# Revision_A.net
KiCad netlist of a schematic drawn in EAGLE
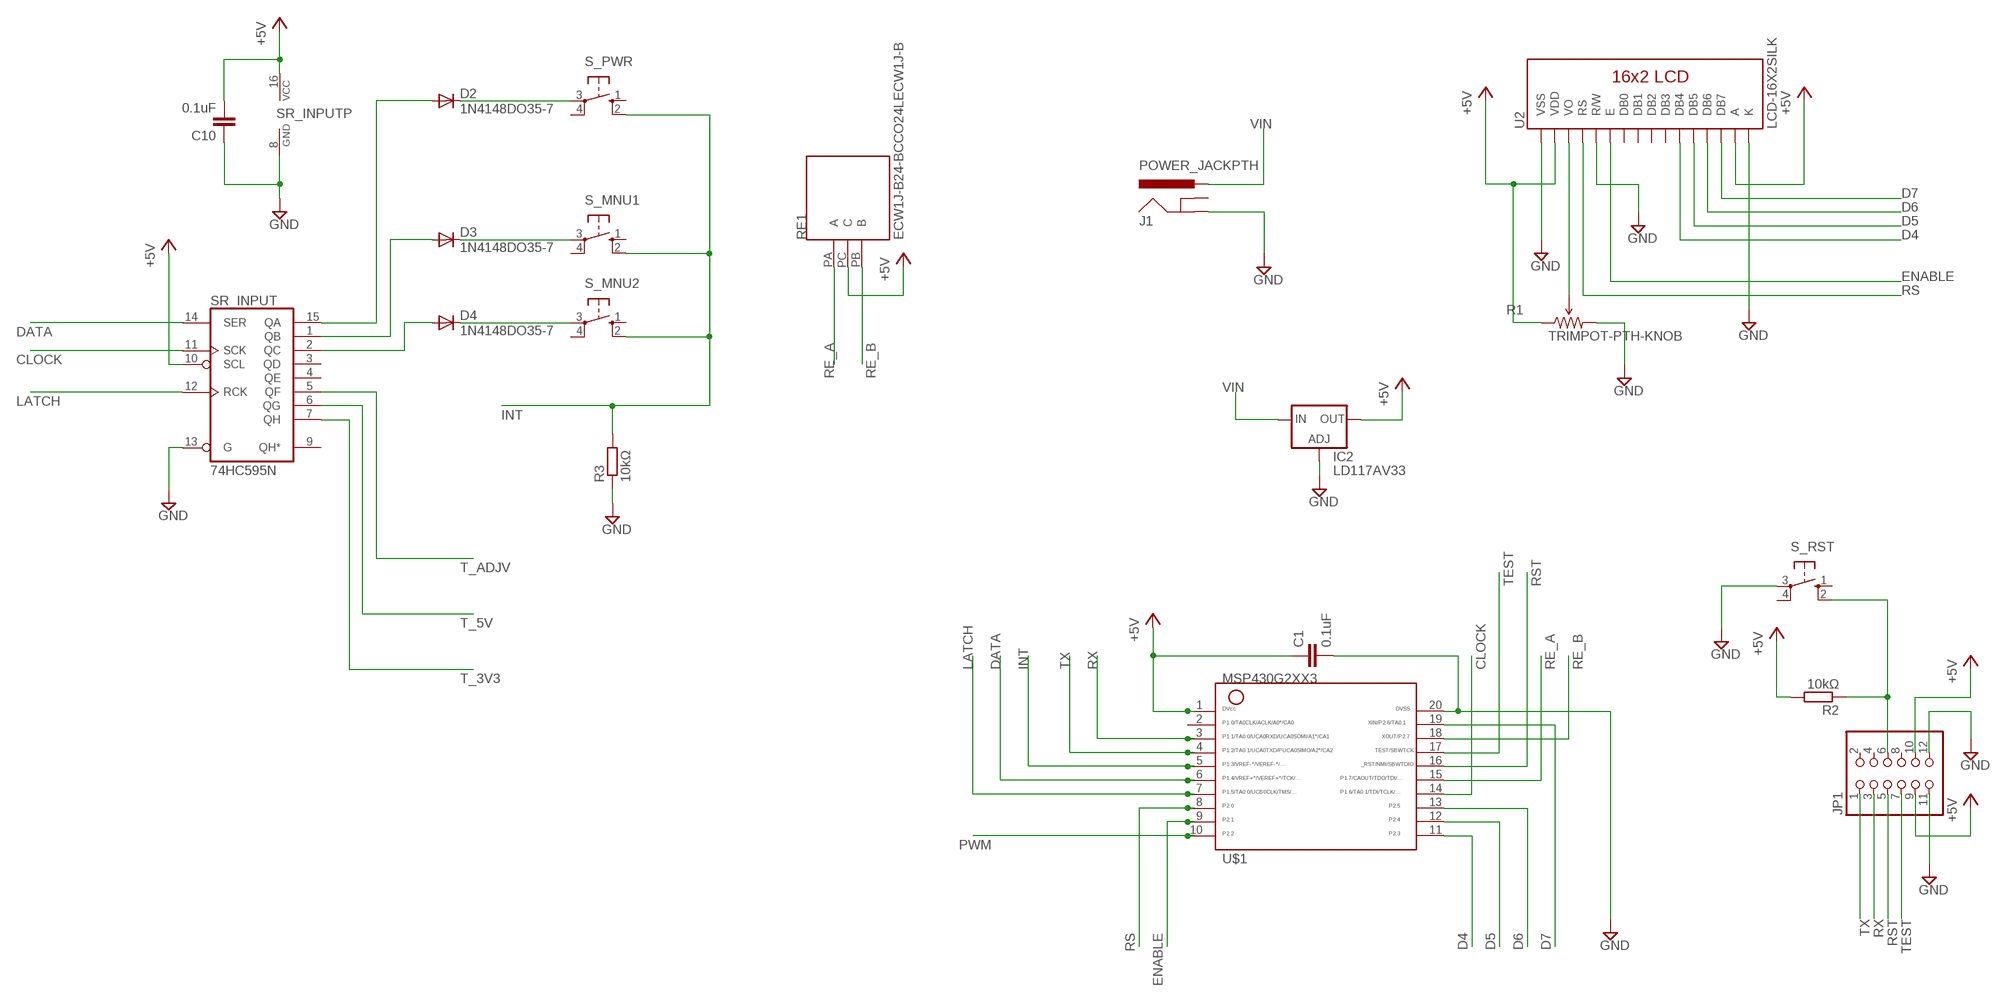
[diagram p0: schematic, sheet 1, part 1 of 2]
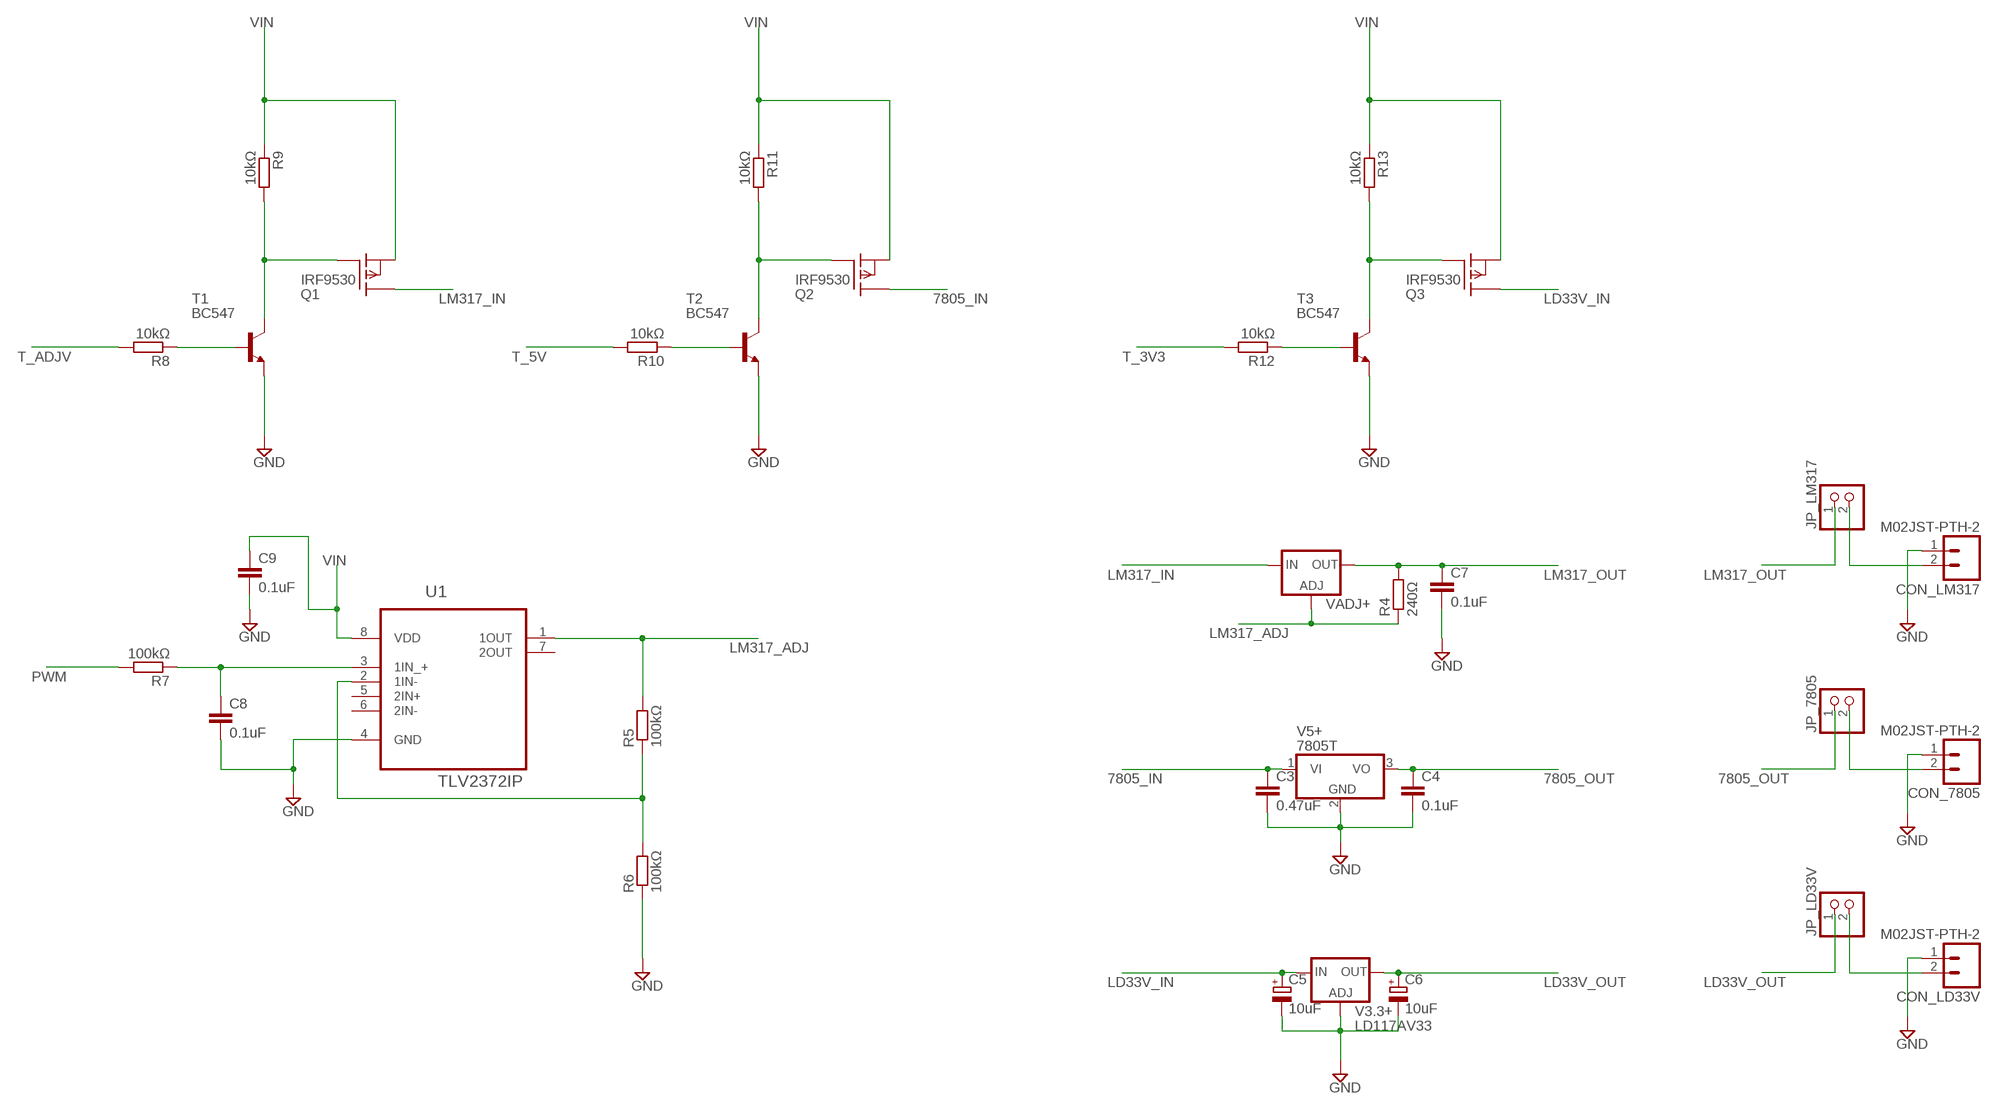
[diagram p1: schematic, sheet 1, part 2 of 2]

(export (version "E")
  (design (tool "Eeschema 10.0.6"))
  (components
    (comp (ref "C1")
      (value "0.1uF")
      (footprint "eagle-import:C025-025X050")
      (libsource (lib "eagle-import") (part "C-EU025-025X050"))
    )
    (comp (ref "C3")
      (value "0.47uF")
      (footprint "eagle-import:C025-025X050")
      (libsource (lib "eagle-import") (part "C-EU025-025X050"))
    )
    (comp (ref "C4")
      (value "0.1uF")
      (footprint "eagle-import:C025-025X050")
      (libsource (lib "eagle-import") (part "C-EU025-025X050"))
    )
    (comp (ref "C5")
      (value "10uF")
      (footprint "eagle-import:E2,5-6")
      (libsource (lib "eagle-import") (part "CPOL-EUE2.5-6"))
    )
    (comp (ref "C6")
      (value "10uF")
      (footprint "eagle-import:E2,5-6")
      (libsource (lib "eagle-import") (part "CPOL-EUE2.5-6"))
    )
    (comp (ref "C7")
      (value "0.1uF")
      (footprint "eagle-import:C025-025X050")
      (libsource (lib "eagle-import") (part "C-EU025-025X050"))
    )
    (comp (ref "C8")
      (value "0.1uF")
      (footprint "eagle-import:C025-025X050")
      (libsource (lib "eagle-import") (part "C-EU025-025X050"))
    )
    (comp (ref "C9")
      (value "0.1uF")
      (footprint "eagle-import:C025-025X050")
      (libsource (lib "eagle-import") (part "C-EU025-025X050"))
    )
    (comp (ref "C10")
      (value "0.1uF")
      (footprint "eagle-import:C025-025X050")
      (libsource (lib "eagle-import") (part "C-EU025-025X050"))
    )
    (comp (ref "CON_7805")
      (value "M02JST-PTH-2")
      (footprint "eagle-import:JST-2-PTH")
      (libsource (lib "eagle-import") (part "M02JST-PTH-2"))
    )
    (comp (ref "CON_LD33V")
      (value "M02JST-PTH-2")
      (footprint "eagle-import:JST-2-PTH")
      (libsource (lib "eagle-import") (part "M02JST-PTH-2"))
    )
    (comp (ref "CON_LM317")
      (value "M02JST-PTH-2")
      (footprint "eagle-import:JST-2-PTH")
      (libsource (lib "eagle-import") (part "M02JST-PTH-2"))
    )
    (comp (ref "D2")
      (value "1N4148DO35-7")
      (footprint "eagle-import:DO35-7")
      (libsource (lib "eagle-import") (part "1N4148DO35-7"))
    )
    (comp (ref "D3")
      (value "1N4148DO35-7")
      (footprint "eagle-import:DO35-7")
      (libsource (lib "eagle-import") (part "1N4148DO35-7"))
    )
    (comp (ref "D4")
      (value "1N4148DO35-7")
      (footprint "eagle-import:DO35-7")
      (libsource (lib "eagle-import") (part "1N4148DO35-7"))
    )
    (comp (ref "IC2")
      (value "LD117AV33")
      (footprint "eagle-import:TO220L1")
      (libsource (lib "eagle-import") (part "LD117A?V33"))
    )
    (comp (ref "J1")
      (value "POWER_JACKPTH")
      (footprint "eagle-import:POWER_JACK_PTH")
      (libsource (lib "eagle-import") (part "POWER_JACKPTH"))
    )
    (comp (ref "JP1")
      (value "PINHD-2X6")
      (footprint "eagle-import:2X06")
      (libsource (lib "eagle-import") (part "PINHD-2X6"))
    )
    (comp (ref "JP_7805")
      (value "PINHD-1X2")
      (footprint "eagle-import:1X02")
      (libsource (lib "eagle-import") (part "PINHD-1X2"))
    )
    (comp (ref "JP_LD33V")
      (value "PINHD-1X2")
      (footprint "eagle-import:1X02")
      (libsource (lib "eagle-import") (part "PINHD-1X2"))
    )
    (comp (ref "JP_LM317")
      (value "PINHD-1X2")
      (footprint "eagle-import:1X02")
      (libsource (lib "eagle-import") (part "PINHD-1X2"))
    )
    (comp (ref "Q1")
      (value "IRF9530")
      (footprint "eagle-import:TO220")
      (libsource (lib "eagle-import") (part "IRF9530"))
    )
    (comp (ref "Q2")
      (value "IRF9530")
      (footprint "eagle-import:TO220")
      (libsource (lib "eagle-import") (part "IRF9530"))
    )
    (comp (ref "Q3")
      (value "IRF9530")
      (footprint "eagle-import:TO220")
      (libsource (lib "eagle-import") (part "IRF9530"))
    )
    (comp (ref "R1")
      (value "TRIMPOT-PTH-KNOB")
      (footprint "eagle-import:3386U")
      (libsource (lib "eagle-import") (part "TRIMPOT-PTH-KNOB"))
    )
    (comp (ref "R2")
      (value "10kΩ")
      (footprint "eagle-import:0207_10")
      (libsource (lib "eagle-import") (part "R-EU_0207/10"))
    )
    (comp (ref "R3")
      (value "10kΩ")
      (footprint "eagle-import:0207_10")
      (libsource (lib "eagle-import") (part "R-EU_0207/10"))
    )
    (comp (ref "R4")
      (value "240Ω")
      (footprint "eagle-import:0207_10")
      (libsource (lib "eagle-import") (part "R-EU_0207/10"))
    )
    (comp (ref "R5")
      (value "100kΩ")
      (footprint "eagle-import:0207_10")
      (libsource (lib "eagle-import") (part "R-EU_0207/10"))
    )
    (comp (ref "R6")
      (value "100kΩ")
      (footprint "eagle-import:0207_10")
      (libsource (lib "eagle-import") (part "R-EU_0207/10"))
    )
    (comp (ref "R7")
      (value "100kΩ")
      (footprint "eagle-import:0207_10")
      (libsource (lib "eagle-import") (part "R-EU_0207/10"))
    )
    (comp (ref "R8")
      (value "10kΩ")
      (footprint "eagle-import:0207_10")
      (libsource (lib "eagle-import") (part "R-EU_0207/10"))
    )
    (comp (ref "R9")
      (value "10kΩ")
      (footprint "eagle-import:0207_10")
      (libsource (lib "eagle-import") (part "R-EU_0207/10"))
    )
    (comp (ref "R10")
      (value "10kΩ")
      (footprint "eagle-import:0207_10")
      (libsource (lib "eagle-import") (part "R-EU_0207/10"))
    )
    (comp (ref "R11")
      (value "10kΩ")
      (footprint "eagle-import:0207_10")
      (libsource (lib "eagle-import") (part "R-EU_0207/10"))
    )
    (comp (ref "R12")
      (value "10kΩ")
      (footprint "eagle-import:0207_10")
      (libsource (lib "eagle-import") (part "R-EU_0207/10"))
    )
    (comp (ref "R13")
      (value "10kΩ")
      (footprint "eagle-import:0207_10")
      (libsource (lib "eagle-import") (part "R-EU_0207/10"))
    )
    (comp (ref "RE1")
      (value "ECW1J-B24-BCCO24LECW1J-B")
      (footprint "eagle-import:ECW1J-B")
      (libsource (lib "eagle-import") (part "ECW1J-B24-BCCO24LECW1J-B"))
    )
    (comp (ref "SR_INPUT")
      (value "74HC595N")
      (footprint "eagle-import:DIL16")
      (libsource (lib "eagle-import") (part "74595NHC"))
    )
    (comp (ref "S_MNU1")
      (value "10-XX")
      (footprint "eagle-import:B3F-10XX")
      (fields (field (name "MPN") "B3F-1000"))
      (libsource (lib "eagle-import") (part "10-XX"))
    )
    (comp (ref "S_MNU2")
      (value "10-XX")
      (footprint "eagle-import:B3F-10XX")
      (fields (field (name "MPN") "B3F-1000"))
      (libsource (lib "eagle-import") (part "10-XX"))
    )
    (comp (ref "S_PWR")
      (value "10-XX")
      (footprint "eagle-import:B3F-10XX")
      (fields (field (name "MPN") "B3F-1000"))
      (libsource (lib "eagle-import") (part "10-XX"))
    )
    (comp (ref "S_RST")
      (value "10-XX")
      (footprint "eagle-import:B3F-10XX")
      (fields (field (name "MPN") "B3F-1000"))
      (libsource (lib "eagle-import") (part "10-XX"))
    )
    (comp (ref "T1")
      (value "BC547")
      (footprint "eagle-import:TO92")
      (libsource (lib "eagle-import") (part "BC547"))
    )
    (comp (ref "T2")
      (value "BC547")
      (footprint "eagle-import:TO92")
      (libsource (lib "eagle-import") (part "BC547"))
    )
    (comp (ref "T3")
      (value "BC547")
      (footprint "eagle-import:TO92")
      (libsource (lib "eagle-import") (part "BC547"))
    )
    (comp (ref "U$1")
      (value "G2XX3---N20")
      (footprint "eagle-import:N20")
      (libsource (lib "eagle-import") (part "G2XX3---N20"))
    )
    (comp (ref "U1")
      (value "TLV2372IP")
      (footprint "eagle-import:DIP254P762X508-8")
      (libsource (lib "eagle-import") (part "TLV2372IP"))
    )
    (comp (ref "U2")
      (value "LCD-16X2SILK")
      (footprint "eagle-import:LCD-16X2")
      (libsource (lib "eagle-import") (part "LCD-16X2SILK"))
    )
    (comp (ref "V3.3+")
      (value "LD117AV33")
      (footprint "eagle-import:TO220L1")
      (libsource (lib "eagle-import") (part "LD117A?V33"))
    )
    (comp (ref "V5+")
      (value "7805T")
      (footprint "eagle-import:TO220H")
      (libsource (lib "eagle-import") (part "78T05"))
    )
    (comp (ref "VADJ+")
      (value "LM317TL")
      (footprint "eagle-import:317TL")
      (libsource (lib "eagle-import") (part "LM317TL"))
    )
  )
  (nets
    (net (code "1") (name "+5V") (class "Default")
      (node (ref "C1") (pin "1") (pinfunction "1_1") (pintype "passive"))
      (node (ref "C10") (pin "2") (pinfunction "2_2") (pintype "passive"))
      (node (ref "IC2") (pin "2") (pinfunction "OUT_2") (pintype "passive"))
      (node (ref "JP1") (pin "10") (pinfunction "10_10") (pintype "passive"))
      (node (ref "JP1") (pin "9") (pinfunction "9_9") (pintype "passive"))
      (node (ref "R1") (pin "1") (pinfunction "CCW_1") (pintype "passive"))
      (node (ref "R2") (pin "2") (pinfunction "2_2") (pintype "passive"))
      (node (ref "RE1") (pin "PC") (pinfunction "C_PC") (pintype "bidirectional"))
      (node (ref "SR_INPUT") (pin "10") (pinfunction "SCL_10") (pintype "input"))
      (node (ref "SR_INPUT") (pin "16") (pinfunction "VCC_16") (pintype "power_in"))
      (node (ref "U$1") (pin "1") (pinfunction "1_1") (pintype "bidirectional"))
      (node (ref "U2") (pin "15") (pinfunction "A_15") (pintype "power_in"))
      (node (ref "U2") (pin "2") (pinfunction "VDD_2") (pintype "power_in"))
    )
    (net (code "2") (name "/7805_IN") (class "Default")
      (node (ref "C3") (pin "1") (pinfunction "1_1") (pintype "passive"))
      (node (ref "Q2") (pin "2") (pinfunction "D_2") (pintype "passive"))
      (node (ref "V5+") (pin "1") (pinfunction "VI_1") (pintype "input"))
    )
    (net (code "3") (name "/7805_OUT") (class "Default")
      (node (ref "C4") (pin "1") (pinfunction "1_1") (pintype "passive"))
      (node (ref "JP_7805") (pin "1") (pinfunction "1_1") (pintype "passive"))
      (node (ref "V5+") (pin "3") (pinfunction "VO_3") (pintype "passive"))
    )
    (net (code "4") (name "/CLOCK") (class "Default")
      (node (ref "SR_INPUT") (pin "11") (pinfunction "SCK_11") (pintype "input"))
      (node (ref "U$1") (pin "14") (pinfunction "14_14") (pintype "bidirectional"))
    )
    (net (code "5") (name "/D4") (class "Default")
      (node (ref "U$1") (pin "11") (pinfunction "11_11") (pintype "bidirectional"))
      (node (ref "U2") (pin "11") (pinfunction "DB4_11") (pintype "bidirectional"))
    )
    (net (code "6") (name "/D5") (class "Default")
      (node (ref "U$1") (pin "12") (pinfunction "12_12") (pintype "bidirectional"))
      (node (ref "U2") (pin "12") (pinfunction "DB5_12") (pintype "bidirectional"))
    )
    (net (code "7") (name "/D6") (class "Default")
      (node (ref "U$1") (pin "13") (pinfunction "13_13") (pintype "bidirectional"))
      (node (ref "U2") (pin "13") (pinfunction "DB6_13") (pintype "bidirectional"))
    )
    (net (code "8") (name "/D7") (class "Default")
      (node (ref "U$1") (pin "19") (pinfunction "19_19") (pintype "bidirectional"))
      (node (ref "U2") (pin "14") (pinfunction "DB7_14") (pintype "bidirectional"))
    )
    (net (code "9") (name "/DATA") (class "Default")
      (node (ref "SR_INPUT") (pin "14") (pinfunction "SER_14") (pintype "input"))
      (node (ref "U$1") (pin "6") (pinfunction "6_6") (pintype "bidirectional"))
    )
    (net (code "10") (name "/ENABLE") (class "Default")
      (node (ref "U$1") (pin "9") (pinfunction "9_9") (pintype "bidirectional"))
      (node (ref "U2") (pin "6") (pinfunction "E_6") (pintype "input"))
    )
    (net (code "11") (name "/INT") (class "Default")
      (node (ref "R3") (pin "2") (pinfunction "2_2") (pintype "passive"))
      (node (ref "S_MNU1") (pin "2") (pinfunction "S1_2") (pintype "passive"))
      (node (ref "S_MNU2") (pin "2") (pinfunction "S1_2") (pintype "passive"))
      (node (ref "S_PWR") (pin "2") (pinfunction "S1_2") (pintype "passive"))
      (node (ref "U$1") (pin "5") (pinfunction "5_5") (pintype "bidirectional"))
    )
    (net (code "12") (name "/LATCH") (class "Default")
      (node (ref "SR_INPUT") (pin "12") (pinfunction "RCK_12") (pintype "input"))
      (node (ref "U$1") (pin "7") (pinfunction "7_7") (pintype "bidirectional"))
    )
    (net (code "13") (name "/LD33V_IN") (class "Default")
      (node (ref "C5") (pin "+") (pinfunction "+_+") (pintype "passive"))
      (node (ref "Q3") (pin "2") (pinfunction "D_2") (pintype "passive"))
      (node (ref "V3.3+") (pin "3") (pinfunction "IN_3") (pintype "input"))
    )
    (net (code "14") (name "/LD33V_OUT") (class "Default")
      (node (ref "C6") (pin "+") (pinfunction "+_+") (pintype "passive"))
      (node (ref "JP_LD33V") (pin "1") (pinfunction "1_1") (pintype "passive"))
      (node (ref "V3.3+") (pin "2") (pinfunction "OUT_2") (pintype "passive"))
    )
    (net (code "15") (name "/LM317_ADJ") (class "Default")
      (node (ref "R4") (pin "1") (pinfunction "1_1") (pintype "passive"))
      (node (ref "R5") (pin "2") (pinfunction "2_2") (pintype "passive"))
      (node (ref "U1") (pin "1") (pinfunction "1OUT_1") (pintype "output"))
      (node (ref "VADJ+") (pin "1") (pinfunction "ADJ_1") (pintype "input"))
    )
    (net (code "16") (name "/LM317_IN") (class "Default")
      (node (ref "Q1") (pin "2") (pinfunction "D_2") (pintype "passive"))
      (node (ref "VADJ+") (pin "3") (pinfunction "IN_3") (pintype "input"))
    )
    (net (code "17") (name "/LM317_OUT") (class "Default")
      (node (ref "C7") (pin "1") (pinfunction "1_1") (pintype "passive"))
      (node (ref "JP_LM317") (pin "1") (pinfunction "1_1") (pintype "passive"))
      (node (ref "R4") (pin "2") (pinfunction "2_2") (pintype "passive"))
      (node (ref "VADJ+") (pin "2") (pinfunction "OUT_2") (pintype "passive"))
    )
    (net (code "18") (name "/PWM") (class "Default")
      (node (ref "R7") (pin "2") (pinfunction "2_2") (pintype "passive"))
      (node (ref "U$1") (pin "10") (pinfunction "10_10") (pintype "bidirectional"))
    )
    (net (code "19") (name "/RE_A") (class "Default")
      (node (ref "RE1") (pin "PA") (pinfunction "A_PA") (pintype "bidirectional"))
      (node (ref "U$1") (pin "15") (pinfunction "15_15") (pintype "bidirectional"))
    )
    (net (code "20") (name "/RE_B") (class "Default")
      (node (ref "RE1") (pin "PB") (pinfunction "B_PB") (pintype "bidirectional"))
      (node (ref "U$1") (pin "18") (pinfunction "18_18") (pintype "bidirectional"))
    )
    (net (code "21") (name "/RS") (class "Default")
      (node (ref "U$1") (pin "8") (pinfunction "8_8") (pintype "bidirectional"))
      (node (ref "U2") (pin "4") (pinfunction "RS_4") (pintype "input"))
    )
    (net (code "22") (name "/RST") (class "Default")
      (node (ref "JP1") (pin "5") (pinfunction "5_5") (pintype "passive"))
      (node (ref "U$1") (pin "16") (pinfunction "16_16") (pintype "bidirectional"))
    )
    (net (code "23") (name "/RX") (class "Default")
      (node (ref "JP1") (pin "3") (pinfunction "3_3") (pintype "passive"))
      (node (ref "U$1") (pin "3") (pinfunction "3_3") (pintype "bidirectional"))
    )
    (net (code "24") (name "/TEST") (class "Default")
      (node (ref "JP1") (pin "7") (pinfunction "7_7") (pintype "passive"))
      (node (ref "U$1") (pin "17") (pinfunction "17_17") (pintype "bidirectional"))
    )
    (net (code "25") (name "/TX") (class "Default")
      (node (ref "JP1") (pin "1") (pinfunction "1_1") (pintype "passive"))
      (node (ref "U$1") (pin "4") (pinfunction "4_4") (pintype "bidirectional"))
    )
    (net (code "26") (name "/T_3V3") (class "Default")
      (node (ref "R12") (pin "2") (pinfunction "2_2") (pintype "passive"))
      (node (ref "SR_INPUT") (pin "7") (pinfunction "QH_7") (pintype "tri_state"))
    )
    (net (code "27") (name "/T_5V") (class "Default")
      (node (ref "R10") (pin "2") (pinfunction "2_2") (pintype "passive"))
      (node (ref "SR_INPUT") (pin "6") (pinfunction "QG_6") (pintype "tri_state"))
    )
    (net (code "28") (name "/T_ADJV") (class "Default")
      (node (ref "R8") (pin "2") (pinfunction "2_2") (pintype "passive"))
      (node (ref "SR_INPUT") (pin "5") (pinfunction "QF_5") (pintype "tri_state"))
    )
    (net (code "29") (name "/VIN") (class "Default")
      (node (ref "C9") (pin "1") (pinfunction "1_1") (pintype "passive"))
      (node (ref "IC2") (pin "3") (pinfunction "IN_3") (pintype "input"))
      (node (ref "J1") (pin "PWR") (pinfunction "PWR_PWR") (pintype "bidirectional"))
      (node (ref "Q1") (pin "3") (pinfunction "S_3") (pintype "passive"))
      (node (ref "Q2") (pin "3") (pinfunction "S_3") (pintype "passive"))
      (node (ref "Q3") (pin "3") (pinfunction "S_3") (pintype "passive"))
      (node (ref "R11") (pin "1") (pinfunction "1_1") (pintype "passive"))
      (node (ref "R13") (pin "1") (pinfunction "1_1") (pintype "passive"))
      (node (ref "R9") (pin "1") (pinfunction "1_1") (pintype "passive"))
      (node (ref "U1") (pin "8") (pinfunction "VDD_8") (pintype "power_in"))
    )
    (net (code "30") (name "GND") (class "Default")
      (node (ref "C1") (pin "2") (pinfunction "2_2") (pintype "passive"))
      (node (ref "C10") (pin "1") (pinfunction "1_1") (pintype "passive"))
      (node (ref "C3") (pin "2") (pinfunction "2_2") (pintype "passive"))
      (node (ref "C4") (pin "2") (pinfunction "2_2") (pintype "passive"))
      (node (ref "C5") (pin "-") (pinfunction "-_-") (pintype "passive"))
      (node (ref "C6") (pin "-") (pinfunction "-_-") (pintype "passive"))
      (node (ref "C7") (pin "2") (pinfunction "2_2") (pintype "passive"))
      (node (ref "C8") (pin "2") (pinfunction "2_2") (pintype "passive"))
      (node (ref "C9") (pin "2") (pinfunction "2_2") (pintype "passive"))
      (node (ref "CON_7805") (pin "1") (pinfunction "1_1") (pintype "passive"))
      (node (ref "CON_LD33V") (pin "1") (pinfunction "1_1") (pintype "passive"))
      (node (ref "CON_LM317") (pin "1") (pinfunction "1_1") (pintype "passive"))
      (node (ref "IC2") (pin "1") (pinfunction "ADJ_1") (pintype "input"))
      (node (ref "J1") (pin "GND") (pinfunction "GND_GND") (pintype "bidirectional"))
      (node (ref "JP1") (pin "11") (pinfunction "11_11") (pintype "passive"))
      (node (ref "JP1") (pin "12") (pinfunction "12_12") (pintype "passive"))
      (node (ref "R1") (pin "3") (pinfunction "CW_3") (pintype "passive"))
      (node (ref "R3") (pin "1") (pinfunction "1_1") (pintype "passive"))
      (node (ref "R6") (pin "1") (pinfunction "1_1") (pintype "passive"))
      (node (ref "SR_INPUT") (pin "13") (pinfunction "G_13") (pintype "input"))
      (node (ref "SR_INPUT") (pin "8") (pinfunction "GND_8") (pintype "power_in"))
      (node (ref "S_RST") (pin "3") (pinfunction "P_3") (pintype "passive"))
      (node (ref "T1") (pin "1") (pinfunction "E_1") (pintype "passive"))
      (node (ref "T2") (pin "1") (pinfunction "E_1") (pintype "passive"))
      (node (ref "T3") (pin "1") (pinfunction "E_1") (pintype "passive"))
      (node (ref "U$1") (pin "20") (pinfunction "20_20") (pintype "bidirectional"))
      (node (ref "U1") (pin "4") (pinfunction "GND_4") (pintype "passive"))
      (node (ref "U2") (pin "1") (pinfunction "VSS_1") (pintype "power_in"))
      (node (ref "U2") (pin "16") (pinfunction "K_16") (pintype "power_in"))
      (node (ref "U2") (pin "5") (pinfunction "R/W_5") (pintype "input"))
      (node (ref "V3.3+") (pin "1") (pinfunction "ADJ_1") (pintype "input"))
      (node (ref "V5+") (pin "2") (pinfunction "GND_2") (pintype "passive"))
    )
    (net (code "31") (name "Net-(CON_7805-Pad2)") (class "Default")
      (node (ref "CON_7805") (pin "2") (pinfunction "2_2") (pintype "passive"))
      (node (ref "JP_7805") (pin "2") (pinfunction "2_2") (pintype "passive"))
    )
    (net (code "32") (name "Net-(CON_LD33V-Pad2)") (class "Default")
      (node (ref "CON_LD33V") (pin "2") (pinfunction "2_2") (pintype "passive"))
      (node (ref "JP_LD33V") (pin "2") (pinfunction "2_2") (pintype "passive"))
    )
    (net (code "33") (name "Net-(CON_LM317-Pad2)") (class "Default")
      (node (ref "CON_LM317") (pin "2") (pinfunction "2_2") (pintype "passive"))
      (node (ref "JP_LM317") (pin "2") (pinfunction "2_2") (pintype "passive"))
    )
    (net (code "34") (name "Net-(Q1-G)") (class "Default")
      (node (ref "Q1") (pin "1") (pinfunction "G_1") (pintype "passive"))
      (node (ref "R9") (pin "2") (pinfunction "2_2") (pintype "passive"))
      (node (ref "T1") (pin "3") (pinfunction "C_3") (pintype "passive"))
    )
    (net (code "35") (name "Net-(Q2-G)") (class "Default")
      (node (ref "Q2") (pin "1") (pinfunction "G_1") (pintype "passive"))
      (node (ref "R11") (pin "2") (pinfunction "2_2") (pintype "passive"))
      (node (ref "T2") (pin "3") (pinfunction "C_3") (pintype "passive"))
    )
    (net (code "36") (name "Net-(Q3-G)") (class "Default")
      (node (ref "Q3") (pin "1") (pinfunction "G_1") (pintype "passive"))
      (node (ref "R13") (pin "2") (pinfunction "2_2") (pintype "passive"))
      (node (ref "T3") (pin "3") (pinfunction "C_3") (pintype "passive"))
    )
    (net (code "37") (name "Net-(R1-WIPER)") (class "Default")
      (node (ref "R1") (pin "2") (pinfunction "WIPER_2") (pintype "passive"))
      (node (ref "U2") (pin "3") (pinfunction "VO_3") (pintype "bidirectional"))
    )
    (net (code "38") (name "Net-(SR_INPUTA-QA)") (class "Default")
      (node (ref "D2") (pin "A") (pinfunction "A_A") (pintype "passive"))
      (node (ref "SR_INPUT") (pin "15") (pinfunction "QA_15") (pintype "tri_state"))
    )
    (net (code "39") (name "Net-(SR_INPUTA-QB)") (class "Default")
      (node (ref "D3") (pin "A") (pinfunction "A_A") (pintype "passive"))
      (node (ref "SR_INPUT") (pin "1") (pinfunction "QB_1") (pintype "tri_state"))
    )
    (net (code "40") (name "Net-(SR_INPUTA-QC)") (class "Default")
      (node (ref "D4") (pin "A") (pinfunction "A_A") (pintype "passive"))
      (node (ref "SR_INPUT") (pin "2") (pinfunction "QC_2") (pintype "tri_state"))
    )
    (net (code "41") (name "Net-(S_MNU1-P)") (class "Default")
      (node (ref "D3") (pin "C") (pinfunction "C_C") (pintype "passive"))
      (node (ref "S_MNU1") (pin "3") (pinfunction "P_3") (pintype "passive"))
    )
    (net (code "42") (name "Net-(S_MNU2-P)") (class "Default")
      (node (ref "D4") (pin "C") (pinfunction "C_C") (pintype "passive"))
      (node (ref "S_MNU2") (pin "3") (pinfunction "P_3") (pintype "passive"))
    )
    (net (code "43") (name "Net-(S_PWR-P)") (class "Default")
      (node (ref "D2") (pin "C") (pinfunction "C_C") (pintype "passive"))
      (node (ref "S_PWR") (pin "3") (pinfunction "P_3") (pintype "passive"))
    )
    (net (code "44") (name "Net-(S_RST-S1)") (class "Default")
      (node (ref "JP1") (pin "6") (pinfunction "6_6") (pintype "passive"))
      (node (ref "R2") (pin "1") (pinfunction "1_1") (pintype "passive"))
      (node (ref "S_RST") (pin "2") (pinfunction "S1_2") (pintype "passive"))
    )
    (net (code "45") (name "Net-(T1-B)") (class "Default")
      (node (ref "R8") (pin "1") (pinfunction "1_1") (pintype "passive"))
      (node (ref "T1") (pin "2") (pinfunction "B_2") (pintype "passive"))
    )
    (net (code "46") (name "Net-(T2-B)") (class "Default")
      (node (ref "R10") (pin "1") (pinfunction "1_1") (pintype "passive"))
      (node (ref "T2") (pin "2") (pinfunction "B_2") (pintype "passive"))
    )
    (net (code "47") (name "Net-(T3-B)") (class "Default")
      (node (ref "R12") (pin "1") (pinfunction "1_1") (pintype "passive"))
      (node (ref "T3") (pin "2") (pinfunction "B_2") (pintype "passive"))
    )
    (net (code "48") (name "Net-(U1-1IN-)") (class "Default")
      (node (ref "R5") (pin "1") (pinfunction "1_1") (pintype "passive"))
      (node (ref "R6") (pin "2") (pinfunction "2_2") (pintype "passive"))
      (node (ref "U1") (pin "2") (pinfunction "1IN-_2") (pintype "input"))
    )
    (net (code "49") (name "Net-(U1-1IN_+)") (class "Default")
      (node (ref "C8") (pin "1") (pinfunction "1_1") (pintype "passive"))
      (node (ref "R7") (pin "1") (pinfunction "1_1") (pintype "passive"))
      (node (ref "U1") (pin "3") (pinfunction "1IN_+_3") (pintype "input"))
    )
    (net (code "50") (name "unconnected-(J1-PadGNDBREAK)") (class "Default")
      (node (ref "J1") (pin "GNDBREAK") (pinfunction "GNDBREAK_GNDBREAK") (pintype "bidirectional"))
    )
    (net (code "51") (name "unconnected-(JP1-Pad2)") (class "Default")
      (node (ref "JP1") (pin "2") (pinfunction "2_2") (pintype "passive"))
    )
    (net (code "52") (name "unconnected-(JP1-Pad4)") (class "Default")
      (node (ref "JP1") (pin "4") (pinfunction "4_4") (pintype "passive"))
    )
    (net (code "53") (name "unconnected-(JP1-Pad8)") (class "Default")
      (node (ref "JP1") (pin "8") (pinfunction "8_8") (pintype "passive"))
    )
    (net (code "54") (name "unconnected-(SR_INPUTA-QD-Pad3)") (class "Default")
      (node (ref "SR_INPUT") (pin "3") (pinfunction "QD_3") (pintype "tri_state"))
    )
    (net (code "55") (name "unconnected-(SR_INPUTA-QE-Pad4)") (class "Default")
      (node (ref "SR_INPUT") (pin "4") (pinfunction "QE_4") (pintype "tri_state"))
    )
    (net (code "56") (name "unconnected-(SR_INPUTA-QH*-Pad9)") (class "Default")
      (node (ref "SR_INPUT") (pin "9") (pinfunction "QH*_9") (pintype "tri_state"))
    )
    (net (code "57") (name "unconnected-(S_MNU1-P1-Pad4)") (class "Default")
      (node (ref "S_MNU1") (pin "4") (pinfunction "P1_4") (pintype "passive"))
    )
    (net (code "58") (name "unconnected-(S_MNU1-S-Pad1)") (class "Default")
      (node (ref "S_MNU1") (pin "1") (pinfunction "S_1") (pintype "passive"))
    )
    (net (code "59") (name "unconnected-(S_MNU2-P1-Pad4)") (class "Default")
      (node (ref "S_MNU2") (pin "4") (pinfunction "P1_4") (pintype "passive"))
    )
    (net (code "60") (name "unconnected-(S_MNU2-S-Pad1)") (class "Default")
      (node (ref "S_MNU2") (pin "1") (pinfunction "S_1") (pintype "passive"))
    )
    (net (code "61") (name "unconnected-(S_PWR-P1-Pad4)") (class "Default")
      (node (ref "S_PWR") (pin "4") (pinfunction "P1_4") (pintype "passive"))
    )
    (net (code "62") (name "unconnected-(S_PWR-S-Pad1)") (class "Default")
      (node (ref "S_PWR") (pin "1") (pinfunction "S_1") (pintype "passive"))
    )
    (net (code "63") (name "unconnected-(S_RST-P1-Pad4)") (class "Default")
      (node (ref "S_RST") (pin "4") (pinfunction "P1_4") (pintype "passive"))
    )
    (net (code "64") (name "unconnected-(S_RST-S-Pad1)") (class "Default")
      (node (ref "S_RST") (pin "1") (pinfunction "S_1") (pintype "passive"))
    )
    (net (code "65") (name "unconnected-(U$1-Pad2)") (class "Default")
      (node (ref "U$1") (pin "2") (pinfunction "2_2") (pintype "bidirectional"))
    )
    (net (code "66") (name "unconnected-(U1-2IN+-Pad5)") (class "Default")
      (node (ref "U1") (pin "5") (pinfunction "2IN+_5") (pintype "input"))
    )
    (net (code "67") (name "unconnected-(U1-2IN--Pad6)") (class "Default")
      (node (ref "U1") (pin "6") (pinfunction "2IN-_6") (pintype "input"))
    )
    (net (code "68") (name "unconnected-(U1-2OUT-Pad7)") (class "Default")
      (node (ref "U1") (pin "7") (pinfunction "2OUT_7") (pintype "output"))
    )
    (net (code "69") (name "unconnected-(U2-DB0-Pad7)") (class "Default")
      (node (ref "U2") (pin "7") (pinfunction "DB0_7") (pintype "bidirectional"))
    )
    (net (code "70") (name "unconnected-(U2-DB1-Pad8)") (class "Default")
      (node (ref "U2") (pin "8") (pinfunction "DB1_8") (pintype "bidirectional"))
    )
    (net (code "71") (name "unconnected-(U2-DB2-Pad9)") (class "Default")
      (node (ref "U2") (pin "9") (pinfunction "DB2_9") (pintype "bidirectional"))
    )
    (net (code "72") (name "unconnected-(U2-DB3-Pad10)") (class "Default")
      (node (ref "U2") (pin "10") (pinfunction "DB3_10") (pintype "bidirectional"))
    )
  )
)
